# Arduino-DUE-SHEILD-4X4-Blank-Pin-Schemat.net
KiCad netlist of a schematic drawn in EAGLE
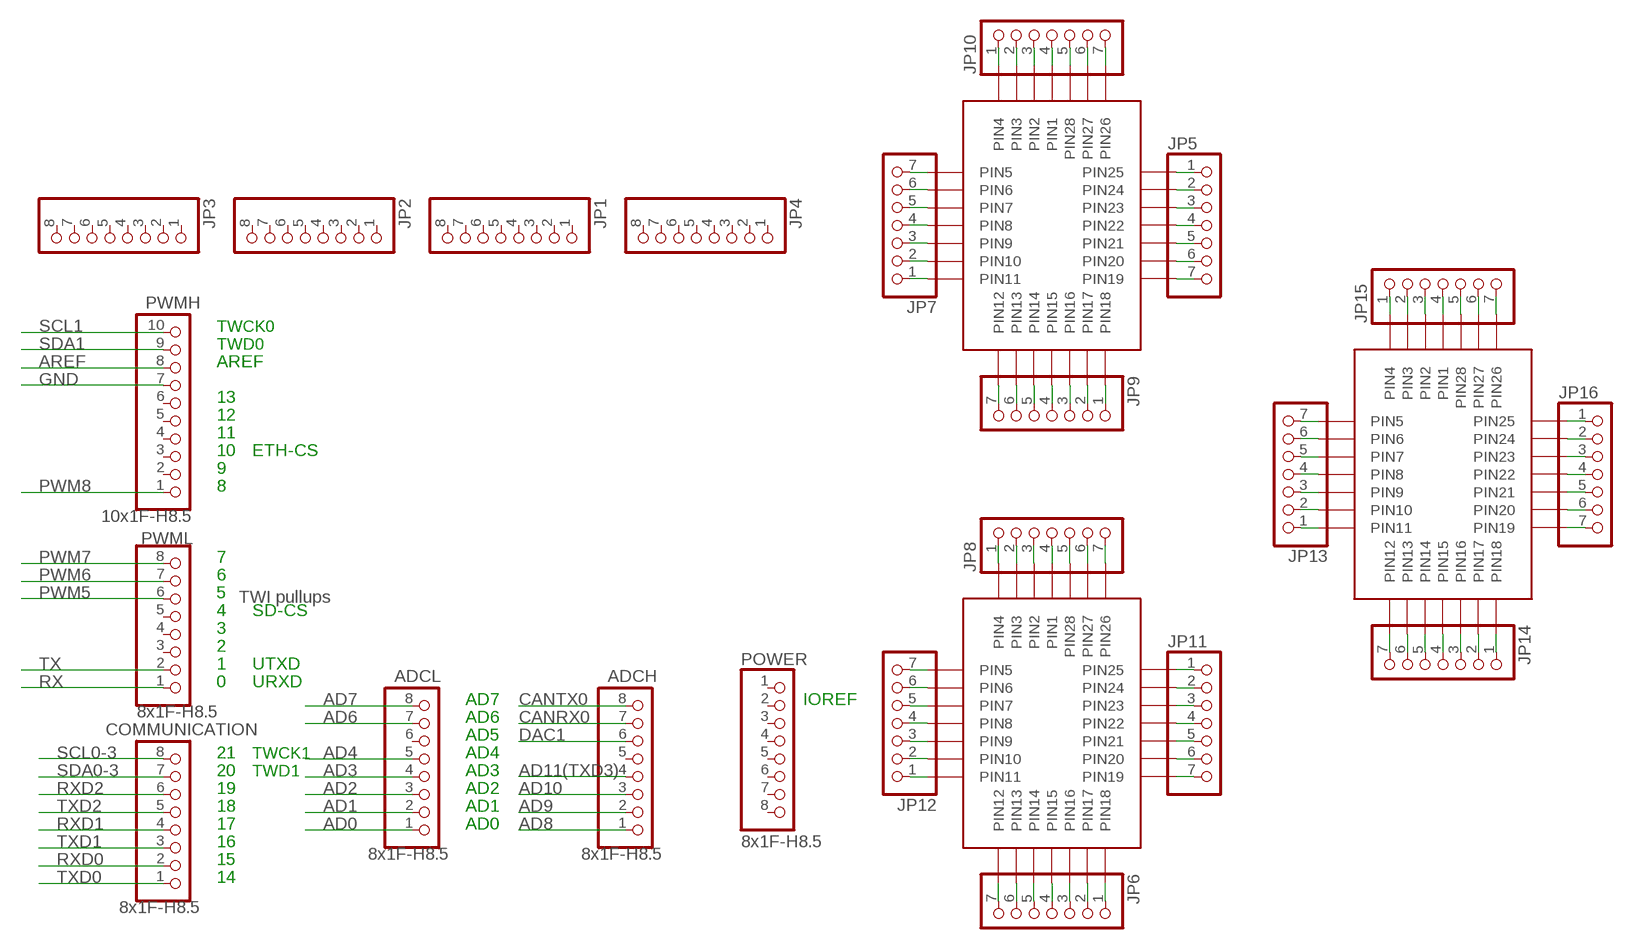
[diagram p0: schematic, sheet 1]

(export (version "E")
  (design (tool "Eeschema 10.0.6"))
  (components
    (comp (ref "ADCH")
      (value "8x1F-H8.5")
      (footprint "eagle-import:1X08")
      (libsource (lib "eagle-import") (part "PINHD-1X8"))
    )
    (comp (ref "ADCL")
      (value "8x1F-H8.5")
      (footprint "eagle-import:1X08")
      (libsource (lib "eagle-import") (part "PINHD-1X8"))
    )
    (comp (ref "COMMUNICATION")
      (value "8x1F-H8.5")
      (footprint "eagle-import:1X08")
      (libsource (lib "eagle-import") (part "PINHD-1X8"))
    )
    (comp (ref "JP1")
      (value "PINHD-1X8")
      (footprint "eagle-import:1X08")
      (libsource (lib "eagle-import") (part "pinhead_PINHD-1X8"))
    )
    (comp (ref "JP2")
      (value "PINHD-1X8")
      (footprint "eagle-import:1X08")
      (libsource (lib "eagle-import") (part "pinhead_PINHD-1X8"))
    )
    (comp (ref "JP3")
      (value "PINHD-1X8")
      (footprint "eagle-import:1X08")
      (libsource (lib "eagle-import") (part "pinhead_PINHD-1X8"))
    )
    (comp (ref "JP4")
      (value "PINHD-1X8")
      (footprint "eagle-import:1X08")
      (libsource (lib "eagle-import") (part "pinhead_PINHD-1X8"))
    )
    (comp (ref "JP5")
      (value "PINHD-1X7")
      (footprint "eagle-import:1X07")
      (libsource (lib "eagle-import") (part "PINHD-1X7"))
    )
    (comp (ref "JP6")
      (value "PINHD-1X7")
      (footprint "eagle-import:1X07")
      (libsource (lib "eagle-import") (part "PINHD-1X7"))
    )
    (comp (ref "JP7")
      (value "PINHD-1X7")
      (footprint "eagle-import:1X07")
      (libsource (lib "eagle-import") (part "PINHD-1X7"))
    )
    (comp (ref "JP8")
      (value "PINHD-1X7")
      (footprint "eagle-import:1X07")
      (libsource (lib "eagle-import") (part "PINHD-1X7"))
    )
    (comp (ref "JP9")
      (value "PINHD-1X7")
      (footprint "eagle-import:1X07")
      (libsource (lib "eagle-import") (part "PINHD-1X7"))
    )
    (comp (ref "JP10")
      (value "PINHD-1X7")
      (footprint "eagle-import:1X07")
      (libsource (lib "eagle-import") (part "PINHD-1X7"))
    )
    (comp (ref "JP11")
      (value "PINHD-1X7")
      (footprint "eagle-import:1X07")
      (libsource (lib "eagle-import") (part "PINHD-1X7"))
    )
    (comp (ref "JP12")
      (value "PINHD-1X7")
      (footprint "eagle-import:1X07")
      (libsource (lib "eagle-import") (part "PINHD-1X7"))
    )
    (comp (ref "JP13")
      (value "PINHD-1X7")
      (footprint "eagle-import:1X07")
      (libsource (lib "eagle-import") (part "PINHD-1X7"))
    )
    (comp (ref "JP14")
      (value "PINHD-1X7")
      (footprint "eagle-import:1X07")
      (libsource (lib "eagle-import") (part "PINHD-1X7"))
    )
    (comp (ref "JP15")
      (value "PINHD-1X7")
      (footprint "eagle-import:1X07")
      (libsource (lib "eagle-import") (part "PINHD-1X7"))
    )
    (comp (ref "JP16")
      (value "PINHD-1X7")
      (footprint "eagle-import:1X07")
      (libsource (lib "eagle-import") (part "PINHD-1X7"))
    )
    (comp (ref "POWER")
      (value "8x1F-H8.5")
      (footprint "eagle-import:1X08")
      (libsource (lib "eagle-import") (part "PINHD-1X8"))
    )
    (comp (ref "PWMH")
      (value "10x1F-H8.5")
      (footprint "eagle-import:1X10")
      (libsource (lib "eagle-import") (part "PINHD-1X10"))
    )
    (comp (ref "PWML")
      (value "8x1F-H8.5")
      (footprint "eagle-import:1X08")
      (libsource (lib "eagle-import") (part "PINHD-1X8"))
    )
    (comp (ref "U$1")
      (value "S28")
      (footprint "eagle-import:S28")
      (libsource (lib "eagle-import") (part "S28"))
    )
    (comp (ref "U$2")
      (value "S28")
      (footprint "eagle-import:S28")
      (libsource (lib "eagle-import") (part "S28"))
    )
    (comp (ref "U$3")
      (value "S28")
      (footprint "eagle-import:S28")
      (libsource (lib "eagle-import") (part "S28"))
    )
  )
  (nets
    (net (code "1") (name "/AD0") (class "Default")
      (node (ref "ADCL") (pin "1") (pinfunction "1_1") (pintype "passive"))
    )
    (net (code "2") (name "/AD1") (class "Default")
      (node (ref "ADCL") (pin "2") (pinfunction "2_2") (pintype "passive"))
    )
    (net (code "3") (name "/AD2") (class "Default")
      (node (ref "ADCL") (pin "3") (pinfunction "3_3") (pintype "passive"))
    )
    (net (code "4") (name "/AD3") (class "Default")
      (node (ref "ADCL") (pin "4") (pinfunction "4_4") (pintype "passive"))
    )
    (net (code "5") (name "/AD4") (class "Default")
      (node (ref "ADCL") (pin "5") (pinfunction "5_5") (pintype "passive"))
    )
    (net (code "6") (name "/AD6") (class "Default")
      (node (ref "ADCL") (pin "7") (pinfunction "7_7") (pintype "passive"))
    )
    (net (code "7") (name "/AD7") (class "Default")
      (node (ref "ADCL") (pin "8") (pinfunction "8_8") (pintype "passive"))
    )
    (net (code "8") (name "/AD8") (class "Default")
      (node (ref "ADCH") (pin "1") (pinfunction "1_1") (pintype "passive"))
    )
    (net (code "9") (name "/AD9") (class "Default")
      (node (ref "ADCH") (pin "2") (pinfunction "2_2") (pintype "passive"))
    )
    (net (code "10") (name "/AD10") (class "Default")
      (node (ref "ADCH") (pin "3") (pinfunction "3_3") (pintype "passive"))
    )
    (net (code "11") (name "/AD11(TXD3)") (class "Default")
      (node (ref "ADCH") (pin "4") (pinfunction "4_4") (pintype "passive"))
    )
    (net (code "12") (name "/AREF") (class "Default")
      (node (ref "PWMH") (pin "8") (pinfunction "8_8") (pintype "passive"))
    )
    (net (code "13") (name "/CANRX0") (class "Default")
      (node (ref "ADCH") (pin "7") (pinfunction "7_7") (pintype "passive"))
    )
    (net (code "14") (name "/CANTX0") (class "Default")
      (node (ref "ADCH") (pin "8") (pinfunction "8_8") (pintype "passive"))
    )
    (net (code "15") (name "/DAC1") (class "Default")
      (node (ref "ADCH") (pin "6") (pinfunction "6_6") (pintype "passive"))
    )
    (net (code "16") (name "/GND") (class "Default")
      (node (ref "PWMH") (pin "7") (pinfunction "7_7") (pintype "passive"))
    )
    (net (code "17") (name "/PWM5") (class "Default")
      (node (ref "PWML") (pin "6") (pinfunction "6_6") (pintype "passive"))
    )
    (net (code "18") (name "/PWM6") (class "Default")
      (node (ref "PWML") (pin "7") (pinfunction "7_7") (pintype "passive"))
    )
    (net (code "19") (name "/PWM7") (class "Default")
      (node (ref "PWML") (pin "8") (pinfunction "8_8") (pintype "passive"))
    )
    (net (code "20") (name "/PWM8") (class "Default")
      (node (ref "PWMH") (pin "1") (pinfunction "1_1") (pintype "passive"))
    )
    (net (code "21") (name "/RX") (class "Default")
      (node (ref "PWML") (pin "1") (pinfunction "1_1") (pintype "passive"))
    )
    (net (code "22") (name "/RXD0") (class "Default")
      (node (ref "COMMUNICATION") (pin "2") (pinfunction "2_2") (pintype "passive"))
    )
    (net (code "23") (name "/RXD1") (class "Default")
      (node (ref "COMMUNICATION") (pin "4") (pinfunction "4_4") (pintype "passive"))
    )
    (net (code "24") (name "/RXD2") (class "Default")
      (node (ref "COMMUNICATION") (pin "6") (pinfunction "6_6") (pintype "passive"))
    )
    (net (code "25") (name "/SCL0-3") (class "Default")
      (node (ref "COMMUNICATION") (pin "8") (pinfunction "8_8") (pintype "passive"))
    )
    (net (code "26") (name "/SCL1") (class "Default")
      (node (ref "PWMH") (pin "10") (pinfunction "10_10") (pintype "passive"))
    )
    (net (code "27") (name "/SDA0-3") (class "Default")
      (node (ref "COMMUNICATION") (pin "7") (pinfunction "7_7") (pintype "passive"))
    )
    (net (code "28") (name "/SDA1") (class "Default")
      (node (ref "PWMH") (pin "9") (pinfunction "9_9") (pintype "passive"))
    )
    (net (code "29") (name "/TX") (class "Default")
      (node (ref "PWML") (pin "2") (pinfunction "2_2") (pintype "passive"))
    )
    (net (code "30") (name "/TXD0") (class "Default")
      (node (ref "COMMUNICATION") (pin "1") (pinfunction "1_1") (pintype "passive"))
    )
    (net (code "31") (name "/TXD1") (class "Default")
      (node (ref "COMMUNICATION") (pin "3") (pinfunction "3_3") (pintype "passive"))
    )
    (net (code "32") (name "/TXD2") (class "Default")
      (node (ref "COMMUNICATION") (pin "5") (pinfunction "5_5") (pintype "passive"))
    )
    (net (code "33") (name "Net-(U$1-PIN1)") (class "Default")
      (node (ref "JP10") (pin "4") (pinfunction "4_4") (pintype "passive"))
      (node (ref "U$1") (pin "1") (pinfunction "PIN1_1") (pintype "bidirectional"))
    )
    (net (code "34") (name "Net-(U$1-PIN2)") (class "Default")
      (node (ref "JP10") (pin "3") (pinfunction "3_3") (pintype "passive"))
      (node (ref "U$1") (pin "2") (pinfunction "PIN2_2") (pintype "bidirectional"))
    )
    (net (code "35") (name "Net-(U$1-PIN3)") (class "Default")
      (node (ref "JP10") (pin "2") (pinfunction "2_2") (pintype "passive"))
      (node (ref "U$1") (pin "3") (pinfunction "PIN3_3") (pintype "bidirectional"))
    )
    (net (code "36") (name "Net-(U$1-PIN4)") (class "Default")
      (node (ref "JP10") (pin "1") (pinfunction "1_1") (pintype "passive"))
      (node (ref "U$1") (pin "4") (pinfunction "PIN4_4") (pintype "bidirectional"))
    )
    (net (code "37") (name "Net-(U$1-PIN5)") (class "Default")
      (node (ref "JP7") (pin "7") (pinfunction "7_7") (pintype "passive"))
      (node (ref "U$1") (pin "5") (pinfunction "PIN5_5") (pintype "bidirectional"))
    )
    (net (code "38") (name "Net-(U$1-PIN6)") (class "Default")
      (node (ref "JP7") (pin "6") (pinfunction "6_6") (pintype "passive"))
      (node (ref "U$1") (pin "6") (pinfunction "PIN6_6") (pintype "bidirectional"))
    )
    (net (code "39") (name "Net-(U$1-PIN7)") (class "Default")
      (node (ref "JP7") (pin "5") (pinfunction "5_5") (pintype "passive"))
      (node (ref "U$1") (pin "7") (pinfunction "PIN7_7") (pintype "bidirectional"))
    )
    (net (code "40") (name "Net-(U$1-PIN8)") (class "Default")
      (node (ref "JP7") (pin "4") (pinfunction "4_4") (pintype "passive"))
      (node (ref "U$1") (pin "8") (pinfunction "PIN8_8") (pintype "bidirectional"))
    )
    (net (code "41") (name "Net-(U$1-PIN9)") (class "Default")
      (node (ref "JP7") (pin "3") (pinfunction "3_3") (pintype "passive"))
      (node (ref "U$1") (pin "9") (pinfunction "PIN9_9") (pintype "bidirectional"))
    )
    (net (code "42") (name "Net-(U$1-PIN10)") (class "Default")
      (node (ref "JP7") (pin "2") (pinfunction "2_2") (pintype "passive"))
      (node (ref "U$1") (pin "10") (pinfunction "PIN10_10") (pintype "bidirectional"))
    )
    (net (code "43") (name "Net-(U$1-PIN11)") (class "Default")
      (node (ref "JP7") (pin "1") (pinfunction "1_1") (pintype "passive"))
      (node (ref "U$1") (pin "11") (pinfunction "PIN11_11") (pintype "bidirectional"))
    )
    (net (code "44") (name "Net-(U$1-PIN12)") (class "Default")
      (node (ref "JP9") (pin "7") (pinfunction "7_7") (pintype "passive"))
      (node (ref "U$1") (pin "12") (pinfunction "PIN12_12") (pintype "bidirectional"))
    )
    (net (code "45") (name "Net-(U$1-PIN13)") (class "Default")
      (node (ref "JP9") (pin "6") (pinfunction "6_6") (pintype "passive"))
      (node (ref "U$1") (pin "13") (pinfunction "PIN13_13") (pintype "bidirectional"))
    )
    (net (code "46") (name "Net-(U$1-PIN14)") (class "Default")
      (node (ref "JP9") (pin "5") (pinfunction "5_5") (pintype "passive"))
      (node (ref "U$1") (pin "14") (pinfunction "PIN14_14") (pintype "bidirectional"))
    )
    (net (code "47") (name "Net-(U$1-PIN15)") (class "Default")
      (node (ref "JP9") (pin "4") (pinfunction "4_4") (pintype "passive"))
      (node (ref "U$1") (pin "15") (pinfunction "PIN15_15") (pintype "bidirectional"))
    )
    (net (code "48") (name "Net-(U$1-PIN16)") (class "Default")
      (node (ref "JP9") (pin "3") (pinfunction "3_3") (pintype "passive"))
      (node (ref "U$1") (pin "16") (pinfunction "PIN16_16") (pintype "bidirectional"))
    )
    (net (code "49") (name "Net-(U$1-PIN17)") (class "Default")
      (node (ref "JP9") (pin "2") (pinfunction "2_2") (pintype "passive"))
      (node (ref "U$1") (pin "17") (pinfunction "PIN17_17") (pintype "bidirectional"))
    )
    (net (code "50") (name "Net-(U$1-PIN18)") (class "Default")
      (node (ref "JP9") (pin "1") (pinfunction "1_1") (pintype "passive"))
      (node (ref "U$1") (pin "18") (pinfunction "PIN18_18") (pintype "bidirectional"))
    )
    (net (code "51") (name "Net-(U$1-PIN19)") (class "Default")
      (node (ref "JP5") (pin "7") (pinfunction "7_7") (pintype "passive"))
      (node (ref "U$1") (pin "19") (pinfunction "PIN19_19") (pintype "bidirectional"))
    )
    (net (code "52") (name "Net-(U$1-PIN20)") (class "Default")
      (node (ref "JP5") (pin "6") (pinfunction "6_6") (pintype "passive"))
      (node (ref "U$1") (pin "20") (pinfunction "PIN20_20") (pintype "bidirectional"))
    )
    (net (code "53") (name "Net-(U$1-PIN21)") (class "Default")
      (node (ref "JP5") (pin "5") (pinfunction "5_5") (pintype "passive"))
      (node (ref "U$1") (pin "21") (pinfunction "PIN21_21") (pintype "bidirectional"))
    )
    (net (code "54") (name "Net-(U$1-PIN22)") (class "Default")
      (node (ref "JP5") (pin "4") (pinfunction "4_4") (pintype "passive"))
      (node (ref "U$1") (pin "22") (pinfunction "PIN22_22") (pintype "bidirectional"))
    )
    (net (code "55") (name "Net-(U$1-PIN23)") (class "Default")
      (node (ref "JP5") (pin "3") (pinfunction "3_3") (pintype "passive"))
      (node (ref "U$1") (pin "23") (pinfunction "PIN23_23") (pintype "bidirectional"))
    )
    (net (code "56") (name "Net-(U$1-PIN24)") (class "Default")
      (node (ref "JP5") (pin "2") (pinfunction "2_2") (pintype "passive"))
      (node (ref "U$1") (pin "24") (pinfunction "PIN24_24") (pintype "bidirectional"))
    )
    (net (code "57") (name "Net-(U$1-PIN25)") (class "Default")
      (node (ref "JP5") (pin "1") (pinfunction "1_1") (pintype "passive"))
      (node (ref "U$1") (pin "25") (pinfunction "PIN25_25") (pintype "bidirectional"))
    )
    (net (code "58") (name "Net-(U$1-PIN26)") (class "Default")
      (node (ref "JP10") (pin "7") (pinfunction "7_7") (pintype "passive"))
      (node (ref "U$1") (pin "26") (pinfunction "PIN26_26") (pintype "bidirectional"))
    )
    (net (code "59") (name "Net-(U$1-PIN27)") (class "Default")
      (node (ref "JP10") (pin "6") (pinfunction "6_6") (pintype "passive"))
      (node (ref "U$1") (pin "27") (pinfunction "PIN27_27") (pintype "bidirectional"))
    )
    (net (code "60") (name "Net-(U$1-PIN28)") (class "Default")
      (node (ref "JP10") (pin "5") (pinfunction "5_5") (pintype "passive"))
      (node (ref "U$1") (pin "28") (pinfunction "PIN28_28") (pintype "bidirectional"))
    )
    (net (code "61") (name "Net-(U$2-PIN1)") (class "Default")
      (node (ref "JP8") (pin "4") (pinfunction "4_4") (pintype "passive"))
      (node (ref "U$2") (pin "1") (pinfunction "PIN1_1") (pintype "bidirectional"))
    )
    (net (code "62") (name "Net-(U$2-PIN2)") (class "Default")
      (node (ref "JP8") (pin "3") (pinfunction "3_3") (pintype "passive"))
      (node (ref "U$2") (pin "2") (pinfunction "PIN2_2") (pintype "bidirectional"))
    )
    (net (code "63") (name "Net-(U$2-PIN3)") (class "Default")
      (node (ref "JP8") (pin "2") (pinfunction "2_2") (pintype "passive"))
      (node (ref "U$2") (pin "3") (pinfunction "PIN3_3") (pintype "bidirectional"))
    )
    (net (code "64") (name "Net-(U$2-PIN4)") (class "Default")
      (node (ref "JP8") (pin "1") (pinfunction "1_1") (pintype "passive"))
      (node (ref "U$2") (pin "4") (pinfunction "PIN4_4") (pintype "bidirectional"))
    )
    (net (code "65") (name "Net-(U$2-PIN5)") (class "Default")
      (node (ref "JP12") (pin "7") (pinfunction "7_7") (pintype "passive"))
      (node (ref "U$2") (pin "5") (pinfunction "PIN5_5") (pintype "bidirectional"))
    )
    (net (code "66") (name "Net-(U$2-PIN6)") (class "Default")
      (node (ref "JP12") (pin "6") (pinfunction "6_6") (pintype "passive"))
      (node (ref "U$2") (pin "6") (pinfunction "PIN6_6") (pintype "bidirectional"))
    )
    (net (code "67") (name "Net-(U$2-PIN7)") (class "Default")
      (node (ref "JP12") (pin "5") (pinfunction "5_5") (pintype "passive"))
      (node (ref "U$2") (pin "7") (pinfunction "PIN7_7") (pintype "bidirectional"))
    )
    (net (code "68") (name "Net-(U$2-PIN8)") (class "Default")
      (node (ref "JP12") (pin "4") (pinfunction "4_4") (pintype "passive"))
      (node (ref "U$2") (pin "8") (pinfunction "PIN8_8") (pintype "bidirectional"))
    )
    (net (code "69") (name "Net-(U$2-PIN9)") (class "Default")
      (node (ref "JP12") (pin "3") (pinfunction "3_3") (pintype "passive"))
      (node (ref "U$2") (pin "9") (pinfunction "PIN9_9") (pintype "bidirectional"))
    )
    (net (code "70") (name "Net-(U$2-PIN10)") (class "Default")
      (node (ref "JP12") (pin "2") (pinfunction "2_2") (pintype "passive"))
      (node (ref "U$2") (pin "10") (pinfunction "PIN10_10") (pintype "bidirectional"))
    )
    (net (code "71") (name "Net-(U$2-PIN11)") (class "Default")
      (node (ref "JP12") (pin "1") (pinfunction "1_1") (pintype "passive"))
      (node (ref "U$2") (pin "11") (pinfunction "PIN11_11") (pintype "bidirectional"))
    )
    (net (code "72") (name "Net-(U$2-PIN12)") (class "Default")
      (node (ref "JP6") (pin "7") (pinfunction "7_7") (pintype "passive"))
      (node (ref "U$2") (pin "12") (pinfunction "PIN12_12") (pintype "bidirectional"))
    )
    (net (code "73") (name "Net-(U$2-PIN13)") (class "Default")
      (node (ref "JP6") (pin "6") (pinfunction "6_6") (pintype "passive"))
      (node (ref "U$2") (pin "13") (pinfunction "PIN13_13") (pintype "bidirectional"))
    )
    (net (code "74") (name "Net-(U$2-PIN14)") (class "Default")
      (node (ref "JP6") (pin "5") (pinfunction "5_5") (pintype "passive"))
      (node (ref "U$2") (pin "14") (pinfunction "PIN14_14") (pintype "bidirectional"))
    )
    (net (code "75") (name "Net-(U$2-PIN15)") (class "Default")
      (node (ref "JP6") (pin "4") (pinfunction "4_4") (pintype "passive"))
      (node (ref "U$2") (pin "15") (pinfunction "PIN15_15") (pintype "bidirectional"))
    )
    (net (code "76") (name "Net-(U$2-PIN16)") (class "Default")
      (node (ref "JP6") (pin "3") (pinfunction "3_3") (pintype "passive"))
      (node (ref "U$2") (pin "16") (pinfunction "PIN16_16") (pintype "bidirectional"))
    )
    (net (code "77") (name "Net-(U$2-PIN17)") (class "Default")
      (node (ref "JP6") (pin "2") (pinfunction "2_2") (pintype "passive"))
      (node (ref "U$2") (pin "17") (pinfunction "PIN17_17") (pintype "bidirectional"))
    )
    (net (code "78") (name "Net-(U$2-PIN18)") (class "Default")
      (node (ref "JP6") (pin "1") (pinfunction "1_1") (pintype "passive"))
      (node (ref "U$2") (pin "18") (pinfunction "PIN18_18") (pintype "bidirectional"))
    )
    (net (code "79") (name "Net-(U$2-PIN19)") (class "Default")
      (node (ref "JP11") (pin "7") (pinfunction "7_7") (pintype "passive"))
      (node (ref "U$2") (pin "19") (pinfunction "PIN19_19") (pintype "bidirectional"))
    )
    (net (code "80") (name "Net-(U$2-PIN20)") (class "Default")
      (node (ref "JP11") (pin "6") (pinfunction "6_6") (pintype "passive"))
      (node (ref "U$2") (pin "20") (pinfunction "PIN20_20") (pintype "bidirectional"))
    )
    (net (code "81") (name "Net-(U$2-PIN21)") (class "Default")
      (node (ref "JP11") (pin "5") (pinfunction "5_5") (pintype "passive"))
      (node (ref "U$2") (pin "21") (pinfunction "PIN21_21") (pintype "bidirectional"))
    )
    (net (code "82") (name "Net-(U$2-PIN22)") (class "Default")
      (node (ref "JP11") (pin "4") (pinfunction "4_4") (pintype "passive"))
      (node (ref "U$2") (pin "22") (pinfunction "PIN22_22") (pintype "bidirectional"))
    )
    (net (code "83") (name "Net-(U$2-PIN23)") (class "Default")
      (node (ref "JP11") (pin "3") (pinfunction "3_3") (pintype "passive"))
      (node (ref "U$2") (pin "23") (pinfunction "PIN23_23") (pintype "bidirectional"))
    )
    (net (code "84") (name "Net-(U$2-PIN24)") (class "Default")
      (node (ref "JP11") (pin "2") (pinfunction "2_2") (pintype "passive"))
      (node (ref "U$2") (pin "24") (pinfunction "PIN24_24") (pintype "bidirectional"))
    )
    (net (code "85") (name "Net-(U$2-PIN25)") (class "Default")
      (node (ref "JP11") (pin "1") (pinfunction "1_1") (pintype "passive"))
      (node (ref "U$2") (pin "25") (pinfunction "PIN25_25") (pintype "bidirectional"))
    )
    (net (code "86") (name "Net-(U$2-PIN26)") (class "Default")
      (node (ref "JP8") (pin "7") (pinfunction "7_7") (pintype "passive"))
      (node (ref "U$2") (pin "26") (pinfunction "PIN26_26") (pintype "bidirectional"))
    )
    (net (code "87") (name "Net-(U$2-PIN27)") (class "Default")
      (node (ref "JP8") (pin "6") (pinfunction "6_6") (pintype "passive"))
      (node (ref "U$2") (pin "27") (pinfunction "PIN27_27") (pintype "bidirectional"))
    )
    (net (code "88") (name "Net-(U$2-PIN28)") (class "Default")
      (node (ref "JP8") (pin "5") (pinfunction "5_5") (pintype "passive"))
      (node (ref "U$2") (pin "28") (pinfunction "PIN28_28") (pintype "bidirectional"))
    )
    (net (code "89") (name "Net-(U$3-PIN1)") (class "Default")
      (node (ref "JP15") (pin "4") (pinfunction "4_4") (pintype "passive"))
      (node (ref "U$3") (pin "1") (pinfunction "PIN1_1") (pintype "bidirectional"))
    )
    (net (code "90") (name "Net-(U$3-PIN2)") (class "Default")
      (node (ref "JP15") (pin "3") (pinfunction "3_3") (pintype "passive"))
      (node (ref "U$3") (pin "2") (pinfunction "PIN2_2") (pintype "bidirectional"))
    )
    (net (code "91") (name "Net-(U$3-PIN3)") (class "Default")
      (node (ref "JP15") (pin "2") (pinfunction "2_2") (pintype "passive"))
      (node (ref "U$3") (pin "3") (pinfunction "PIN3_3") (pintype "bidirectional"))
    )
    (net (code "92") (name "Net-(U$3-PIN4)") (class "Default")
      (node (ref "JP15") (pin "1") (pinfunction "1_1") (pintype "passive"))
      (node (ref "U$3") (pin "4") (pinfunction "PIN4_4") (pintype "bidirectional"))
    )
    (net (code "93") (name "Net-(U$3-PIN5)") (class "Default")
      (node (ref "JP13") (pin "7") (pinfunction "7_7") (pintype "passive"))
      (node (ref "U$3") (pin "5") (pinfunction "PIN5_5") (pintype "bidirectional"))
    )
    (net (code "94") (name "Net-(U$3-PIN6)") (class "Default")
      (node (ref "JP13") (pin "6") (pinfunction "6_6") (pintype "passive"))
      (node (ref "U$3") (pin "6") (pinfunction "PIN6_6") (pintype "bidirectional"))
    )
    (net (code "95") (name "Net-(U$3-PIN7)") (class "Default")
      (node (ref "JP13") (pin "5") (pinfunction "5_5") (pintype "passive"))
      (node (ref "U$3") (pin "7") (pinfunction "PIN7_7") (pintype "bidirectional"))
    )
    (net (code "96") (name "Net-(U$3-PIN8)") (class "Default")
      (node (ref "JP13") (pin "4") (pinfunction "4_4") (pintype "passive"))
      (node (ref "U$3") (pin "8") (pinfunction "PIN8_8") (pintype "bidirectional"))
    )
    (net (code "97") (name "Net-(U$3-PIN9)") (class "Default")
      (node (ref "JP13") (pin "3") (pinfunction "3_3") (pintype "passive"))
      (node (ref "U$3") (pin "9") (pinfunction "PIN9_9") (pintype "bidirectional"))
    )
    (net (code "98") (name "Net-(U$3-PIN10)") (class "Default")
      (node (ref "JP13") (pin "2") (pinfunction "2_2") (pintype "passive"))
      (node (ref "U$3") (pin "10") (pinfunction "PIN10_10") (pintype "bidirectional"))
    )
    (net (code "99") (name "Net-(U$3-PIN11)") (class "Default")
      (node (ref "JP13") (pin "1") (pinfunction "1_1") (pintype "passive"))
      (node (ref "U$3") (pin "11") (pinfunction "PIN11_11") (pintype "bidirectional"))
    )
    (net (code "100") (name "Net-(U$3-PIN12)") (class "Default")
      (node (ref "JP14") (pin "7") (pinfunction "7_7") (pintype "passive"))
      (node (ref "U$3") (pin "12") (pinfunction "PIN12_12") (pintype "bidirectional"))
    )
    (net (code "101") (name "Net-(U$3-PIN13)") (class "Default")
      (node (ref "JP14") (pin "6") (pinfunction "6_6") (pintype "passive"))
      (node (ref "U$3") (pin "13") (pinfunction "PIN13_13") (pintype "bidirectional"))
    )
    (net (code "102") (name "Net-(U$3-PIN14)") (class "Default")
      (node (ref "JP14") (pin "5") (pinfunction "5_5") (pintype "passive"))
      (node (ref "U$3") (pin "14") (pinfunction "PIN14_14") (pintype "bidirectional"))
    )
    (net (code "103") (name "Net-(U$3-PIN15)") (class "Default")
      (node (ref "JP14") (pin "4") (pinfunction "4_4") (pintype "passive"))
      (node (ref "U$3") (pin "15") (pinfunction "PIN15_15") (pintype "bidirectional"))
    )
    (net (code "104") (name "Net-(U$3-PIN16)") (class "Default")
      (node (ref "JP14") (pin "3") (pinfunction "3_3") (pintype "passive"))
      (node (ref "U$3") (pin "16") (pinfunction "PIN16_16") (pintype "bidirectional"))
    )
    (net (code "105") (name "Net-(U$3-PIN17)") (class "Default")
      (node (ref "JP14") (pin "2") (pinfunction "2_2") (pintype "passive"))
      (node (ref "U$3") (pin "17") (pinfunction "PIN17_17") (pintype "bidirectional"))
    )
    (net (code "106") (name "Net-(U$3-PIN18)") (class "Default")
      (node (ref "JP14") (pin "1") (pinfunction "1_1") (pintype "passive"))
      (node (ref "U$3") (pin "18") (pinfunction "PIN18_18") (pintype "bidirectional"))
    )
    (net (code "107") (name "Net-(U$3-PIN19)") (class "Default")
      (node (ref "JP16") (pin "7") (pinfunction "7_7") (pintype "passive"))
      (node (ref "U$3") (pin "19") (pinfunction "PIN19_19") (pintype "bidirectional"))
    )
    (net (code "108") (name "Net-(U$3-PIN20)") (class "Default")
      (node (ref "JP16") (pin "6") (pinfunction "6_6") (pintype "passive"))
      (node (ref "U$3") (pin "20") (pinfunction "PIN20_20") (pintype "bidirectional"))
    )
    (net (code "109") (name "Net-(U$3-PIN21)") (class "Default")
      (node (ref "JP16") (pin "5") (pinfunction "5_5") (pintype "passive"))
      (node (ref "U$3") (pin "21") (pinfunction "PIN21_21") (pintype "bidirectional"))
    )
    (net (code "110") (name "Net-(U$3-PIN22)") (class "Default")
      (node (ref "JP16") (pin "4") (pinfunction "4_4") (pintype "passive"))
      (node (ref "U$3") (pin "22") (pinfunction "PIN22_22") (pintype "bidirectional"))
    )
    (net (code "111") (name "Net-(U$3-PIN23)") (class "Default")
      (node (ref "JP16") (pin "3") (pinfunction "3_3") (pintype "passive"))
      (node (ref "U$3") (pin "23") (pinfunction "PIN23_23") (pintype "bidirectional"))
    )
    (net (code "112") (name "Net-(U$3-PIN24)") (class "Default")
      (node (ref "JP16") (pin "2") (pinfunction "2_2") (pintype "passive"))
      (node (ref "U$3") (pin "24") (pinfunction "PIN24_24") (pintype "bidirectional"))
    )
    (net (code "113") (name "Net-(U$3-PIN25)") (class "Default")
      (node (ref "JP16") (pin "1") (pinfunction "1_1") (pintype "passive"))
      (node (ref "U$3") (pin "25") (pinfunction "PIN25_25") (pintype "bidirectional"))
    )
    (net (code "114") (name "Net-(U$3-PIN26)") (class "Default")
      (node (ref "JP15") (pin "7") (pinfunction "7_7") (pintype "passive"))
      (node (ref "U$3") (pin "26") (pinfunction "PIN26_26") (pintype "bidirectional"))
    )
    (net (code "115") (name "Net-(U$3-PIN27)") (class "Default")
      (node (ref "JP15") (pin "6") (pinfunction "6_6") (pintype "passive"))
      (node (ref "U$3") (pin "27") (pinfunction "PIN27_27") (pintype "bidirectional"))
    )
    (net (code "116") (name "Net-(U$3-PIN28)") (class "Default")
      (node (ref "JP15") (pin "5") (pinfunction "5_5") (pintype "passive"))
      (node (ref "U$3") (pin "28") (pinfunction "PIN28_28") (pintype "bidirectional"))
    )
    (net (code "117") (name "unconnected-(ADCH-Pad5)") (class "Default")
      (node (ref "ADCH") (pin "5") (pinfunction "5_5") (pintype "passive"))
    )
    (net (code "118") (name "unconnected-(ADCL-Pad6)") (class "Default")
      (node (ref "ADCL") (pin "6") (pinfunction "6_6") (pintype "passive"))
    )
    (net (code "119") (name "unconnected-(JP1-Pad1)") (class "Default")
      (node (ref "JP1") (pin "1") (pinfunction "1_1") (pintype "passive"))
    )
    (net (code "120") (name "unconnected-(JP1-Pad2)") (class "Default")
      (node (ref "JP1") (pin "2") (pinfunction "2_2") (pintype "passive"))
    )
    (net (code "121") (name "unconnected-(JP1-Pad3)") (class "Default")
      (node (ref "JP1") (pin "3") (pinfunction "3_3") (pintype "passive"))
    )
    (net (code "122") (name "unconnected-(JP1-Pad4)") (class "Default")
      (node (ref "JP1") (pin "4") (pinfunction "4_4") (pintype "passive"))
    )
    (net (code "123") (name "unconnected-(JP1-Pad5)") (class "Default")
      (node (ref "JP1") (pin "5") (pinfunction "5_5") (pintype "passive"))
    )
    (net (code "124") (name "unconnected-(JP1-Pad6)") (class "Default")
      (node (ref "JP1") (pin "6") (pinfunction "6_6") (pintype "passive"))
    )
    (net (code "125") (name "unconnected-(JP1-Pad7)") (class "Default")
      (node (ref "JP1") (pin "7") (pinfunction "7_7") (pintype "passive"))
    )
    (net (code "126") (name "unconnected-(JP1-Pad8)") (class "Default")
      (node (ref "JP1") (pin "8") (pinfunction "8_8") (pintype "passive"))
    )
    (net (code "127") (name "unconnected-(JP2-Pad1)") (class "Default")
      (node (ref "JP2") (pin "1") (pinfunction "1_1") (pintype "passive"))
    )
    (net (code "128") (name "unconnected-(JP2-Pad2)") (class "Default")
      (node (ref "JP2") (pin "2") (pinfunction "2_2") (pintype "passive"))
    )
    (net (code "129") (name "unconnected-(JP2-Pad3)") (class "Default")
      (node (ref "JP2") (pin "3") (pinfunction "3_3") (pintype "passive"))
    )
    (net (code "130") (name "unconnected-(JP2-Pad4)") (class "Default")
      (node (ref "JP2") (pin "4") (pinfunction "4_4") (pintype "passive"))
    )
    (net (code "131") (name "unconnected-(JP2-Pad5)") (class "Default")
      (node (ref "JP2") (pin "5") (pinfunction "5_5") (pintype "passive"))
    )
    (net (code "132") (name "unconnected-(JP2-Pad6)") (class "Default")
      (node (ref "JP2") (pin "6") (pinfunction "6_6") (pintype "passive"))
    )
    (net (code "133") (name "unconnected-(JP2-Pad7)") (class "Default")
      (node (ref "JP2") (pin "7") (pinfunction "7_7") (pintype "passive"))
    )
    (net (code "134") (name "unconnected-(JP2-Pad8)") (class "Default")
      (node (ref "JP2") (pin "8") (pinfunction "8_8") (pintype "passive"))
    )
    (net (code "135") (name "unconnected-(JP3-Pad1)") (class "Default")
      (node (ref "JP3") (pin "1") (pinfunction "1_1") (pintype "passive"))
    )
    (net (code "136") (name "unconnected-(JP3-Pad2)") (class "Default")
      (node (ref "JP3") (pin "2") (pinfunction "2_2") (pintype "passive"))
    )
    (net (code "137") (name "unconnected-(JP3-Pad3)") (class "Default")
      (node (ref "JP3") (pin "3") (pinfunction "3_3") (pintype "passive"))
    )
    (net (code "138") (name "unconnected-(JP3-Pad4)") (class "Default")
      (node (ref "JP3") (pin "4") (pinfunction "4_4") (pintype "passive"))
    )
    (net (code "139") (name "unconnected-(JP3-Pad5)") (class "Default")
      (node (ref "JP3") (pin "5") (pinfunction "5_5") (pintype "passive"))
    )
    (net (code "140") (name "unconnected-(JP3-Pad6)") (class "Default")
      (node (ref "JP3") (pin "6") (pinfunction "6_6") (pintype "passive"))
    )
    (net (code "141") (name "unconnected-(JP3-Pad7)") (class "Default")
      (node (ref "JP3") (pin "7") (pinfunction "7_7") (pintype "passive"))
    )
    (net (code "142") (name "unconnected-(JP3-Pad8)") (class "Default")
      (node (ref "JP3") (pin "8") (pinfunction "8_8") (pintype "passive"))
    )
    (net (code "143") (name "unconnected-(JP4-Pad1)") (class "Default")
      (node (ref "JP4") (pin "1") (pinfunction "1_1") (pintype "passive"))
    )
    (net (code "144") (name "unconnected-(JP4-Pad2)") (class "Default")
      (node (ref "JP4") (pin "2") (pinfunction "2_2") (pintype "passive"))
    )
    (net (code "145") (name "unconnected-(JP4-Pad3)") (class "Default")
      (node (ref "JP4") (pin "3") (pinfunction "3_3") (pintype "passive"))
    )
    (net (code "146") (name "unconnected-(JP4-Pad4)") (class "Default")
      (node (ref "JP4") (pin "4") (pinfunction "4_4") (pintype "passive"))
    )
    (net (code "147") (name "unconnected-(JP4-Pad5)") (class "Default")
      (node (ref "JP4") (pin "5") (pinfunction "5_5") (pintype "passive"))
    )
    (net (code "148") (name "unconnected-(JP4-Pad6)") (class "Default")
      (node (ref "JP4") (pin "6") (pinfunction "6_6") (pintype "passive"))
    )
    (net (code "149") (name "unconnected-(JP4-Pad7)") (class "Default")
      (node (ref "JP4") (pin "7") (pinfunction "7_7") (pintype "passive"))
    )
    (net (code "150") (name "unconnected-(JP4-Pad8)") (class "Default")
      (node (ref "JP4") (pin "8") (pinfunction "8_8") (pintype "passive"))
    )
    (net (code "151") (name "unconnected-(POWER-Pad1)") (class "Default")
      (node (ref "POWER") (pin "1") (pinfunction "1_1") (pintype "passive"))
    )
    (net (code "152") (name "unconnected-(POWER-Pad2)") (class "Default")
      (node (ref "POWER") (pin "2") (pinfunction "2_2") (pintype "passive"))
    )
    (net (code "153") (name "unconnected-(POWER-Pad3)") (class "Default")
      (node (ref "POWER") (pin "3") (pinfunction "3_3") (pintype "passive"))
    )
    (net (code "154") (name "unconnected-(POWER-Pad4)") (class "Default")
      (node (ref "POWER") (pin "4") (pinfunction "4_4") (pintype "passive"))
    )
    (net (code "155") (name "unconnected-(POWER-Pad5)") (class "Default")
      (node (ref "POWER") (pin "5") (pinfunction "5_5") (pintype "passive"))
    )
    (net (code "156") (name "unconnected-(POWER-Pad6)") (class "Default")
      (node (ref "POWER") (pin "6") (pinfunction "6_6") (pintype "passive"))
    )
    (net (code "157") (name "unconnected-(POWER-Pad7)") (class "Default")
      (node (ref "POWER") (pin "7") (pinfunction "7_7") (pintype "passive"))
    )
    (net (code "158") (name "unconnected-(POWER-Pad8)") (class "Default")
      (node (ref "POWER") (pin "8") (pinfunction "8_8") (pintype "passive"))
    )
    (net (code "159") (name "unconnected-(PWMH-Pad2)") (class "Default")
      (node (ref "PWMH") (pin "2") (pinfunction "2_2") (pintype "passive"))
    )
    (net (code "160") (name "unconnected-(PWMH-Pad3)") (class "Default")
      (node (ref "PWMH") (pin "3") (pinfunction "3_3") (pintype "passive"))
    )
    (net (code "161") (name "unconnected-(PWMH-Pad4)") (class "Default")
      (node (ref "PWMH") (pin "4") (pinfunction "4_4") (pintype "passive"))
    )
    (net (code "162") (name "unconnected-(PWMH-Pad5)") (class "Default")
      (node (ref "PWMH") (pin "5") (pinfunction "5_5") (pintype "passive"))
    )
    (net (code "163") (name "unconnected-(PWMH-Pad6)") (class "Default")
      (node (ref "PWMH") (pin "6") (pinfunction "6_6") (pintype "passive"))
    )
    (net (code "164") (name "unconnected-(PWML-Pad3)") (class "Default")
      (node (ref "PWML") (pin "3") (pinfunction "3_3") (pintype "passive"))
    )
    (net (code "165") (name "unconnected-(PWML-Pad4)") (class "Default")
      (node (ref "PWML") (pin "4") (pinfunction "4_4") (pintype "passive"))
    )
    (net (code "166") (name "unconnected-(PWML-Pad5)") (class "Default")
      (node (ref "PWML") (pin "5") (pinfunction "5_5") (pintype "passive"))
    )
  )
)
